# v1.net
KiCad netlist of a schematic drawn in EAGLE
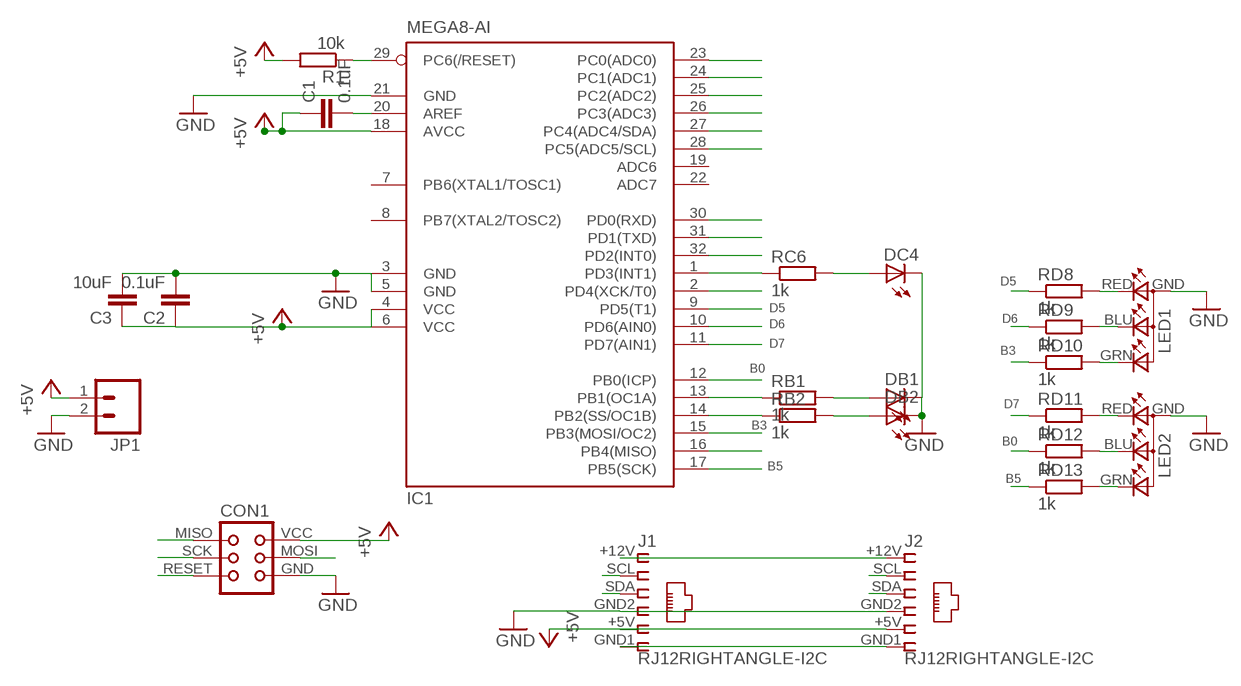
[diagram p0: schematic, sheet 1]

(export (version "E")
  (design (tool "Eeschema 10.0.6"))
  (components
    (comp (ref "C1")
      (value "0.1uF")
      (footprint "eagle-import:C1206")
      (libsource (lib "eagle-import") (part "C-EUC1206"))
    )
    (comp (ref "C2")
      (value "0.1uF")
      (footprint "eagle-import:C1206")
      (libsource (lib "eagle-import") (part "C-EUC1206"))
    )
    (comp (ref "C3")
      (value "10uF")
      (footprint "eagle-import:C1206")
      (libsource (lib "eagle-import") (part "C-EUC1206"))
    )
    (comp (ref "CON1")
      (value "TINYISP")
      (footprint "eagle-import:TINYISP")
      (libsource (lib "eagle-import") (part "TINYISP"))
    )
    (comp (ref "DB1")
      (value "LED3MM")
      (footprint "eagle-import:LED3MM")
      (libsource (lib "eagle-import") (part "LED3MM"))
    )
    (comp (ref "DB2")
      (value "LED3MM")
      (footprint "eagle-import:LED3MM")
      (libsource (lib "eagle-import") (part "LED3MM"))
    )
    (comp (ref "DC4")
      (value "LED3MM")
      (footprint "eagle-import:LED3MM")
      (libsource (lib "eagle-import") (part "LED3MM"))
    )
    (comp (ref "IC1")
      (value "MEGA8-AI")
      (footprint "eagle-import:TQFP32-08")
      (fields (field (name "MPN") "ATMEGA8-16AU"))
      (libsource (lib "eagle-import") (part "MEGA8-AI"))
    )
    (comp (ref "J1")
      (value "RJ12RIGHTANGLE-I2C")
      (footprint "eagle-import:RJ12-RIGHTANGLE-I2C")
      (libsource (lib "eagle-import") (part "RJ12RIGHTANGLE-I2C"))
    )
    (comp (ref "J2")
      (value "RJ12RIGHTANGLE-I2C")
      (footprint "eagle-import:RJ12-RIGHTANGLE-I2C")
      (libsource (lib "eagle-import") (part "RJ12RIGHTANGLE-I2C"))
    )
    (comp (ref "JP1")
      (value "M023.5MM")
      (footprint "eagle-import:SCREWTERMINAL-3.5MM-2")
      (libsource (lib "eagle-import") (part "M023.5MM"))
    )
    (comp (ref "LED1")
      (value "TOPLED-3")
      (footprint "eagle-import:LED-TRICOLOR-THROUGHHOLE")
      (libsource (lib "eagle-import") (part "TOPLED-3"))
    )
    (comp (ref "LED2")
      (value "TOPLED-3")
      (footprint "eagle-import:LED-TRICOLOR-THROUGHHOLE")
      (libsource (lib "eagle-import") (part "TOPLED-3"))
    )
    (comp (ref "R1")
      (value "10k")
      (footprint "eagle-import:M1206")
      (libsource (lib "eagle-import") (part "R-EU_M1206"))
    )
    (comp (ref "RB1")
      (value "1k")
      (footprint "eagle-import:M1206")
      (libsource (lib "eagle-import") (part "R-EU_M1206"))
    )
    (comp (ref "RB2")
      (value "1k")
      (footprint "eagle-import:M1206")
      (libsource (lib "eagle-import") (part "R-EU_M1206"))
    )
    (comp (ref "RC6")
      (value "1k")
      (footprint "eagle-import:M1206")
      (libsource (lib "eagle-import") (part "R-EU_M1206"))
    )
    (comp (ref "RD8")
      (value "1k")
      (footprint "eagle-import:M1206")
      (libsource (lib "eagle-import") (part "R-EU_M1206"))
    )
    (comp (ref "RD9")
      (value "1k")
      (footprint "eagle-import:M1206")
      (libsource (lib "eagle-import") (part "R-EU_M1206"))
    )
    (comp (ref "RD10")
      (value "1k")
      (footprint "eagle-import:M1206")
      (libsource (lib "eagle-import") (part "R-EU_M1206"))
    )
    (comp (ref "RD11")
      (value "1k")
      (footprint "eagle-import:M1206")
      (libsource (lib "eagle-import") (part "R-EU_M1206"))
    )
    (comp (ref "RD12")
      (value "1k")
      (footprint "eagle-import:M1206")
      (libsource (lib "eagle-import") (part "R-EU_M1206"))
    )
    (comp (ref "RD13")
      (value "1k")
      (footprint "eagle-import:M1206")
      (libsource (lib "eagle-import") (part "R-EU_M1206"))
    )
  )
  (nets
    (net (code "1") (name "+5V") (class "Default")
      (node (ref "C1") (pin "1") (pinfunction "1_1") (pintype "passive"))
      (node (ref "C2") (pin "1") (pinfunction "1_1") (pintype "passive"))
      (node (ref "C3") (pin "1") (pinfunction "1_1") (pintype "passive"))
      (node (ref "CON1") (pin "VCC") (pinfunction "VCC_VCC") (pintype "passive"))
      (node (ref "IC1") (pin "18") (pinfunction "AVCC_18") (pintype "power_in"))
      (node (ref "IC1") (pin "4") (pinfunction "VCC_4") (pintype "power_in"))
      (node (ref "IC1") (pin "6") (pinfunction "VCC_6") (pintype "power_in"))
      (node (ref "J1") (pin "+5V") (pinfunction "5_+5V") (pintype "power_in"))
      (node (ref "J2") (pin "+5V") (pinfunction "5_+5V") (pintype "power_in"))
      (node (ref "JP1") (pin "1") (pinfunction "1_1") (pintype "passive"))
      (node (ref "R1") (pin "2") (pinfunction "2_2") (pintype "passive"))
    )
    (net (code "2") (name "/B0") (class "Default")
      (node (ref "IC1") (pin "12") (pinfunction "PB0(ICP)_12") (pintype "bidirectional"))
      (node (ref "RD12") (pin "1") (pinfunction "1_1") (pintype "passive"))
    )
    (net (code "3") (name "/B3") (class "Default")
      (node (ref "IC1") (pin "15") (pinfunction "PB3(MOSI/OC2)_15") (pintype "bidirectional"))
      (node (ref "RD10") (pin "1") (pinfunction "1_1") (pintype "passive"))
    )
    (net (code "4") (name "/B5") (class "Default")
      (node (ref "IC1") (pin "17") (pinfunction "PB5(SCK)_17") (pintype "bidirectional"))
      (node (ref "RD13") (pin "1") (pinfunction "1_1") (pintype "passive"))
    )
    (net (code "5") (name "/D5") (class "Default")
      (node (ref "IC1") (pin "9") (pinfunction "PD5(T1)_9") (pintype "bidirectional"))
      (node (ref "RD8") (pin "1") (pinfunction "1_1") (pintype "passive"))
    )
    (net (code "6") (name "/D6") (class "Default")
      (node (ref "IC1") (pin "10") (pinfunction "PD6(AIN0)_10") (pintype "bidirectional"))
      (node (ref "RD9") (pin "1") (pinfunction "1_1") (pintype "passive"))
    )
    (net (code "7") (name "/D7") (class "Default")
      (node (ref "IC1") (pin "11") (pinfunction "PD7(AIN1)_11") (pintype "bidirectional"))
      (node (ref "RD11") (pin "1") (pinfunction "1_1") (pintype "passive"))
    )
    (net (code "8") (name "/MISO") (class "Default")
      (node (ref "CON1") (pin "MISO") (pinfunction "MISO_MISO") (pintype "passive"))
      (node (ref "IC1") (pin "16") (pinfunction "PB4(MISO)_16") (pintype "bidirectional"))
    )
    (net (code "9") (name "/RESET") (class "Default")
      (node (ref "CON1") (pin "RESET") (pinfunction "RESET_RESET") (pintype "passive"))
      (node (ref "IC1") (pin "29") (pinfunction "PC6(/RESET)_29") (pintype "bidirectional"))
      (node (ref "R1") (pin "1") (pinfunction "1_1") (pintype "passive"))
    )
    (net (code "10") (name "/SCL") (class "Default")
      (node (ref "IC1") (pin "28") (pinfunction "PC5(ADC5/SCL)_28") (pintype "bidirectional"))
      (node (ref "J1") (pin "SCL") (pinfunction "2_SCL") (pintype "bidirectional"))
      (node (ref "J2") (pin "SCL") (pinfunction "2_SCL") (pintype "bidirectional"))
    )
    (net (code "11") (name "/SDA") (class "Default")
      (node (ref "IC1") (pin "27") (pinfunction "PC4(ADC4/SDA)_27") (pintype "bidirectional"))
      (node (ref "J1") (pin "SDA") (pinfunction "3_SDA") (pintype "bidirectional"))
      (node (ref "J2") (pin "SDA") (pinfunction "3_SDA") (pintype "bidirectional"))
    )
    (net (code "12") (name "GND") (class "Default")
      (node (ref "C2") (pin "2") (pinfunction "2_2") (pintype "passive"))
      (node (ref "C3") (pin "2") (pinfunction "2_2") (pintype "passive"))
      (node (ref "CON1") (pin "GND") (pinfunction "GND_GND") (pintype "passive"))
      (node (ref "DB1") (pin "K") (pinfunction "C_K") (pintype "passive"))
      (node (ref "DB2") (pin "K") (pinfunction "C_K") (pintype "passive"))
      (node (ref "DC4") (pin "K") (pinfunction "C_K") (pintype "passive"))
      (node (ref "IC1") (pin "21") (pinfunction "GND_21") (pintype "power_in"))
      (node (ref "IC1") (pin "3") (pinfunction "GND_3") (pintype "power_in"))
      (node (ref "IC1") (pin "5") (pinfunction "GND_5") (pintype "power_in"))
      (node (ref "J1") (pin "GND2") (pinfunction "4_GND2") (pintype "power_in"))
      (node (ref "J2") (pin "GND2") (pinfunction "4_GND2") (pintype "power_in"))
      (node (ref "JP1") (pin "2") (pinfunction "2_2") (pintype "passive"))
      (node (ref "LED1") (pin "GND") (pinfunction "A2_GND") (pintype "passive"))
      (node (ref "LED2") (pin "GND") (pinfunction "A2_GND") (pintype "passive"))
    )
    (net (code "13") (name "Net-(DB1-PadA)") (class "Default")
      (node (ref "DB1") (pin "A") (pinfunction "A_A") (pintype "passive"))
      (node (ref "RB1") (pin "2") (pinfunction "2_2") (pintype "passive"))
    )
    (net (code "14") (name "Net-(DB2-PadA)") (class "Default")
      (node (ref "DB2") (pin "A") (pinfunction "A_A") (pintype "passive"))
      (node (ref "RB2") (pin "2") (pinfunction "2_2") (pintype "passive"))
    )
    (net (code "15") (name "Net-(DC4-PadA)") (class "Default")
      (node (ref "DC4") (pin "A") (pinfunction "A_A") (pintype "passive"))
      (node (ref "RC6") (pin "2") (pinfunction "2_2") (pintype "passive"))
    )
    (net (code "16") (name "Net-(IC1-AREF)") (class "Default")
      (node (ref "C1") (pin "2") (pinfunction "2_2") (pintype "passive"))
      (node (ref "IC1") (pin "20") (pinfunction "AREF_20") (pintype "passive"))
    )
    (net (code "17") (name "Net-(IC1-PB1(OC1A))") (class "Default")
      (node (ref "IC1") (pin "13") (pinfunction "PB1(OC1A)_13") (pintype "bidirectional"))
      (node (ref "RB1") (pin "1") (pinfunction "1_1") (pintype "passive"))
    )
    (net (code "18") (name "Net-(IC1-PB2(SS{slash}OC1B))") (class "Default")
      (node (ref "IC1") (pin "14") (pinfunction "PB2(SS/OC1B)_14") (pintype "bidirectional"))
      (node (ref "RB2") (pin "1") (pinfunction "1_1") (pintype "passive"))
    )
    (net (code "19") (name "Net-(IC1-PD3(INT1))") (class "Default")
      (node (ref "IC1") (pin "1") (pinfunction "PD3(INT1)_1") (pintype "bidirectional"))
      (node (ref "RC6") (pin "1") (pinfunction "1_1") (pintype "passive"))
    )
    (net (code "20") (name "Net-(J1-1)") (class "Default")
      (node (ref "J1") (pin "+12V") (pinfunction "1_+12V") (pintype "power_in"))
      (node (ref "J2") (pin "+12V") (pinfunction "1_+12V") (pintype "power_in"))
    )
    (net (code "21") (name "Net-(J1-6)") (class "Default")
      (node (ref "J1") (pin "GND1") (pinfunction "6_GND1") (pintype "power_in"))
      (node (ref "J2") (pin "GND1") (pinfunction "6_GND1") (pintype "power_in"))
    )
    (net (code "22") (name "Net-(LED1-CBLUE)") (class "Default")
      (node (ref "LED1") (pin "BLU") (pinfunction "CBLUE_BLU") (pintype "passive"))
      (node (ref "RD9") (pin "2") (pinfunction "2_2") (pintype "passive"))
    )
    (net (code "23") (name "Net-(LED1-CGREEN)") (class "Default")
      (node (ref "LED1") (pin "GRN") (pinfunction "CGREEN_GRN") (pintype "passive"))
      (node (ref "RD10") (pin "2") (pinfunction "2_2") (pintype "passive"))
    )
    (net (code "24") (name "Net-(LED1-CRED)") (class "Default")
      (node (ref "LED1") (pin "RED") (pinfunction "CRED_RED") (pintype "passive"))
      (node (ref "RD8") (pin "2") (pinfunction "2_2") (pintype "passive"))
    )
    (net (code "25") (name "Net-(LED2-CBLUE)") (class "Default")
      (node (ref "LED2") (pin "BLU") (pinfunction "CBLUE_BLU") (pintype "passive"))
      (node (ref "RD12") (pin "2") (pinfunction "2_2") (pintype "passive"))
    )
    (net (code "26") (name "Net-(LED2-CGREEN)") (class "Default")
      (node (ref "LED2") (pin "GRN") (pinfunction "CGREEN_GRN") (pintype "passive"))
      (node (ref "RD13") (pin "2") (pinfunction "2_2") (pintype "passive"))
    )
    (net (code "27") (name "Net-(LED2-CRED)") (class "Default")
      (node (ref "LED2") (pin "RED") (pinfunction "CRED_RED") (pintype "passive"))
      (node (ref "RD11") (pin "2") (pinfunction "2_2") (pintype "passive"))
    )
    (net (code "28") (name "unconnected-(CON1-PadMOSI)") (class "Default")
      (node (ref "CON1") (pin "MOSI") (pinfunction "MOSI_MOSI") (pintype "passive"))
    )
    (net (code "29") (name "unconnected-(CON1-PadSCK)") (class "Default")
      (node (ref "CON1") (pin "SCK") (pinfunction "SCK_SCK") (pintype "passive"))
    )
    (net (code "30") (name "unconnected-(IC1-ADC6-Pad19)") (class "Default")
      (node (ref "IC1") (pin "19") (pinfunction "ADC6_19") (pintype "bidirectional"))
    )
    (net (code "31") (name "unconnected-(IC1-ADC7-Pad22)") (class "Default")
      (node (ref "IC1") (pin "22") (pinfunction "ADC7_22") (pintype "bidirectional"))
    )
    (net (code "32") (name "unconnected-(IC1-PB6(XTAL1{slash}TOSC1)-Pad7)") (class "Default")
      (node (ref "IC1") (pin "7") (pinfunction "PB6(XTAL1/TOSC1)_7") (pintype "bidirectional"))
    )
    (net (code "33") (name "unconnected-(IC1-PB7(XTAL2{slash}TOSC2)-Pad8)") (class "Default")
      (node (ref "IC1") (pin "8") (pinfunction "PB7(XTAL2/TOSC2)_8") (pintype "bidirectional"))
    )
    (net (code "34") (name "unconnected-(IC1-PC0(ADC0)-Pad23)") (class "Default")
      (node (ref "IC1") (pin "23") (pinfunction "PC0(ADC0)_23") (pintype "bidirectional"))
    )
    (net (code "35") (name "unconnected-(IC1-PC1(ADC1)-Pad24)") (class "Default")
      (node (ref "IC1") (pin "24") (pinfunction "PC1(ADC1)_24") (pintype "bidirectional"))
    )
    (net (code "36") (name "unconnected-(IC1-PC2(ADC2)-Pad25)") (class "Default")
      (node (ref "IC1") (pin "25") (pinfunction "PC2(ADC2)_25") (pintype "bidirectional"))
    )
    (net (code "37") (name "unconnected-(IC1-PC3(ADC3)-Pad26)") (class "Default")
      (node (ref "IC1") (pin "26") (pinfunction "PC3(ADC3)_26") (pintype "bidirectional"))
    )
    (net (code "38") (name "unconnected-(IC1-PD0(RXD)-Pad30)") (class "Default")
      (node (ref "IC1") (pin "30") (pinfunction "PD0(RXD)_30") (pintype "bidirectional"))
    )
    (net (code "39") (name "unconnected-(IC1-PD1(TXD)-Pad31)") (class "Default")
      (node (ref "IC1") (pin "31") (pinfunction "PD1(TXD)_31") (pintype "bidirectional"))
    )
    (net (code "40") (name "unconnected-(IC1-PD2(INT0)-Pad32)") (class "Default")
      (node (ref "IC1") (pin "32") (pinfunction "PD2(INT0)_32") (pintype "bidirectional"))
    )
    (net (code "41") (name "unconnected-(IC1-PD4(XCK{slash}T0)-Pad2)") (class "Default")
      (node (ref "IC1") (pin "2") (pinfunction "PD4(XCK/T0)_2") (pintype "bidirectional"))
    )
  )
)
